# PulseOX.net
KiCad netlist of a schematic drawn in EAGLE
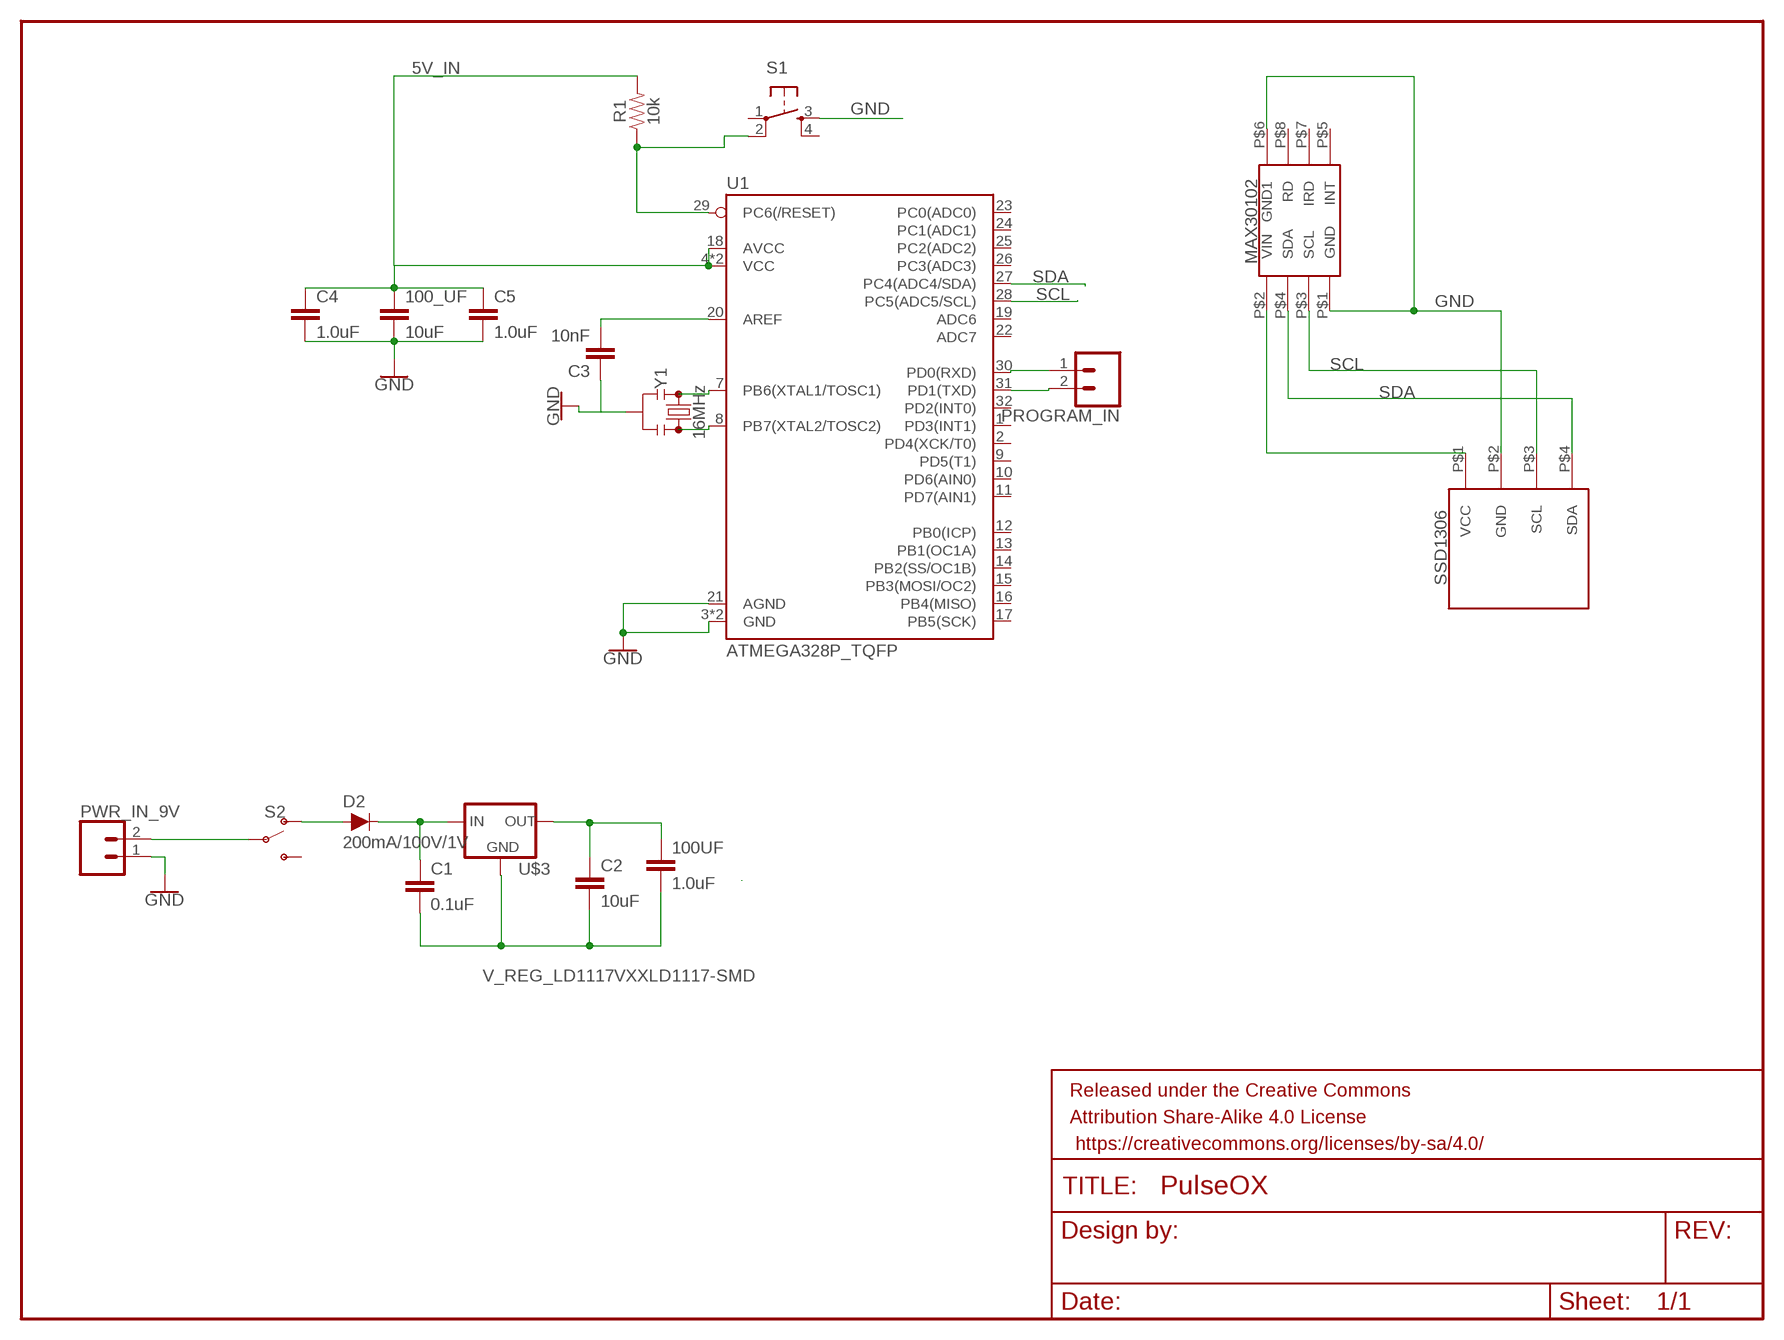
[diagram p0: schematic, sheet 1]

(export (version "E")
  (design (tool "Eeschema 10.0.6"))
  (components
    (comp (ref "100UF")
      (value "1.0uF")
      (footprint "eagle-import:1206")
      (libsource (lib "eagle-import") (part "1.0UF-1206-50V-10%"))
    )
    (comp (ref "100_UF")
      (value "10uF")
      (footprint "eagle-import:1206")
      (libsource (lib "eagle-import") (part "10UF-1206-6.3V-20%"))
    )
    (comp (ref "C1")
      (value "0.1uF")
      (footprint "eagle-import:0603")
      (libsource (lib "eagle-import") (part "0.1UF-0603-25V-(+80/-20%)"))
    )
    (comp (ref "C2")
      (value "10uF")
      (footprint "eagle-import:0603")
      (libsource (lib "eagle-import") (part "10UF-0603-6.3V-20%"))
    )
    (comp (ref "C3")
      (value "10nF")
      (footprint "eagle-import:0603")
      (libsource (lib "eagle-import") (part "10NF-0603-50V-10%"))
    )
    (comp (ref "C4")
      (value "1.0uF")
      (footprint "eagle-import:0603")
      (libsource (lib "eagle-import") (part "1.0UF-0603-16V-10%"))
    )
    (comp (ref "C5")
      (value "1.0uF")
      (footprint "eagle-import:0603")
      (libsource (lib "eagle-import") (part "1.0UF-0603-16V-10%"))
    )
    (comp (ref "D2")
      (value "200mA/100V/1V")
      (footprint "eagle-import:DIODE-1N4148")
      (libsource (lib "eagle-import") (part "DIODE-1N4148"))
    )
    (comp (ref "FRAME1")
      (value "FRAME-LETTER")
      (footprint "eagle-import:CREATIVE_COMMONS")
      (libsource (lib "eagle-import") (part "FRAME-LETTER"))
    )
    (comp (ref "PROGRAM_IN")
      (value "CONN_02")
      (footprint "eagle-import:1X02")
      (libsource (lib "eagle-import") (part "CONN_02"))
    )
    (comp (ref "PWR_IN_9V")
      (value "CONN_02")
      (footprint "eagle-import:1X02")
      (libsource (lib "eagle-import") (part "CONN_02"))
    )
    (comp (ref "R1")
      (value "10k")
      (footprint "eagle-import:0603")
      (libsource (lib "eagle-import") (part "10KOHM-0603-1/10W-1%"))
    )
    (comp (ref "S1")
      (value "TAC_SWITCHPTH")
      (footprint "eagle-import:TACTILE-PTH")
      (libsource (lib "eagle-import") (part "TAC_SWITCHPTH"))
    )
    (comp (ref "S2")
      (value "SWITCH-SPDT-PTH-11.6X4.0MM")
      (footprint "eagle-import:SWITCH_SPDT_PTH_11.6X4.0MM")
      (libsource (lib "eagle-import") (part "SWITCH-SPDT-PTH-11.6X4.0MM"))
    )
    (comp (ref "U$1")
      (value "MAX30102")
      (footprint "eagle-import:MAX30102")
      (libsource (lib "eagle-import") (part "MAX30102"))
    )
    (comp (ref "U$2")
      (value "SSD1306")
      (footprint "eagle-import:SSD1306")
      (libsource (lib "eagle-import") (part "SSD1306"))
    )
    (comp (ref "U$3")
      (value "V_REG_LD1117VXXLD1117-SMD")
      (footprint "eagle-import:SOT223")
      (libsource (lib "eagle-import") (part "V_REG_LD1117VXXLD1117-SMD"))
    )
    (comp (ref "U1")
      (value "ATMEGA328P_TQFP")
      (footprint "eagle-import:TQFP32-08")
      (libsource (lib "eagle-import") (part "ATMEGA328P_TQFP"))
    )
    (comp (ref "Y1")
      (value "16MHz")
      (footprint "eagle-import:RESONATOR-SMD-3.2X1.3")
      (libsource (lib "eagle-import") (part "RESONATOR-16MHZSMD_3.2X1.3"))
    )
  )
  (nets
    (net (code "1") (name "/5V_IN") (class "Default")
      (node (ref "100_UF") (pin "1") (pinfunction "1_1") (pintype "passive"))
      (node (ref "C4") (pin "1") (pinfunction "1_1") (pintype "passive"))
      (node (ref "C5") (pin "1") (pinfunction "1_1") (pintype "passive"))
      (node (ref "R1") (pin "2") (pinfunction "2_2") (pintype "passive"))
      (node (ref "U1") (pin "18") (pinfunction "AVCC_18") (pintype "bidirectional"))
      (node (ref "U1") (pin "4") (pinfunction "VCC_4") (pintype "bidirectional"))
      (node (ref "U1") (pin "6") (pinfunction "VCC_6") (pintype "bidirectional"))
    )
    (net (code "2") (name "/SCL") (class "Default")
      (node (ref "U$1") (pin "P$3") (pinfunction "SCL_P$3") (pintype "bidirectional"))
      (node (ref "U$2") (pin "P$3") (pinfunction "SCL_P$3") (pintype "bidirectional"))
      (node (ref "U1") (pin "28") (pinfunction "PC5(ADC5/SCL)_28") (pintype "bidirectional"))
    )
    (net (code "3") (name "/SDA") (class "Default")
      (node (ref "U$1") (pin "P$4") (pinfunction "SDA_P$4") (pintype "bidirectional"))
      (node (ref "U$2") (pin "P$4") (pinfunction "SDA_P$4") (pintype "bidirectional"))
      (node (ref "U1") (pin "27") (pinfunction "PC4(ADC4/SDA)_27") (pintype "bidirectional"))
    )
    (net (code "4") (name "GND") (class "Default")
      (node (ref "100_UF") (pin "2") (pinfunction "2_2") (pintype "passive"))
      (node (ref "C3") (pin "1") (pinfunction "1_1") (pintype "passive"))
      (node (ref "C4") (pin "2") (pinfunction "2_2") (pintype "passive"))
      (node (ref "C5") (pin "2") (pinfunction "2_2") (pintype "passive"))
      (node (ref "PWR_IN_9V") (pin "1") (pinfunction "1_1") (pintype "passive"))
      (node (ref "S1") (pin "3") (pinfunction "3_3") (pintype "passive"))
      (node (ref "U$1") (pin "P$1") (pinfunction "GND_P$1") (pintype "bidirectional"))
      (node (ref "U$1") (pin "P$6") (pinfunction "GND1_P$6") (pintype "bidirectional"))
      (node (ref "U$2") (pin "P$2") (pinfunction "GND_P$2") (pintype "bidirectional"))
      (node (ref "U1") (pin "21") (pinfunction "AGND_21") (pintype "bidirectional"))
      (node (ref "U1") (pin "3") (pinfunction "GND_3") (pintype "bidirectional"))
      (node (ref "U1") (pin "5") (pinfunction "GND_5") (pintype "bidirectional"))
      (node (ref "Y1") (pin "2") (pinfunction "2_2") (pintype "passive"))
    )
    (net (code "5") (name "Net-(S2-O)") (class "Default")
      (node (ref "D2") (pin "A") (pinfunction "A_A") (pintype "passive"))
      (node (ref "S2") (pin "1") (pinfunction "O_1") (pintype "passive"))
    )
    (net (code "6") (name "Net-(S2-P)") (class "Default")
      (node (ref "PWR_IN_9V") (pin "2") (pinfunction "2_2") (pintype "passive"))
      (node (ref "S2") (pin "2") (pinfunction "P_2") (pintype "passive"))
    )
    (net (code "7") (name "Net-(U$1-VIN)") (class "Default")
      (node (ref "U$1") (pin "P$2") (pinfunction "VIN_P$2") (pintype "bidirectional"))
      (node (ref "U$2") (pin "P$1") (pinfunction "VCC_P$1") (pintype "bidirectional"))
    )
    (net (code "8") (name "Net-(U$3-GND)") (class "Default")
      (node (ref "100UF") (pin "2") (pinfunction "2_2") (pintype "passive"))
      (node (ref "C1") (pin "2") (pinfunction "2_2") (pintype "passive"))
      (node (ref "C2") (pin "2") (pinfunction "2_2") (pintype "passive"))
      (node (ref "U$3") (pin "1") (pinfunction "GND_1") (pintype "input"))
    )
    (net (code "9") (name "Net-(U$3-IN)") (class "Default")
      (node (ref "C1") (pin "1") (pinfunction "1_1") (pintype "passive"))
      (node (ref "D2") (pin "C") (pinfunction "C_C") (pintype "passive"))
      (node (ref "U$3") (pin "3") (pinfunction "IN_3") (pintype "input"))
    )
    (net (code "10") (name "Net-(U$3-OUT)") (class "Default")
      (node (ref "100UF") (pin "1") (pinfunction "1_1") (pintype "passive"))
      (node (ref "C2") (pin "1") (pinfunction "1_1") (pintype "passive"))
      (node (ref "U$3") (pin "2") (pinfunction "OUT_2") (pintype "passive"))
    )
    (net (code "11") (name "Net-(U1-AREF)") (class "Default")
      (node (ref "C3") (pin "2") (pinfunction "2_2") (pintype "passive"))
      (node (ref "U1") (pin "20") (pinfunction "AREF_20") (pintype "bidirectional"))
    )
    (net (code "12") (name "Net-(U1-PB6(XTAL1{slash}TOSC1))") (class "Default")
      (node (ref "U1") (pin "7") (pinfunction "PB6(XTAL1/TOSC1)_7") (pintype "bidirectional"))
      (node (ref "Y1") (pin "1") (pinfunction "1_1") (pintype "passive"))
    )
    (net (code "13") (name "Net-(U1-PB7(XTAL2{slash}TOSC2))") (class "Default")
      (node (ref "U1") (pin "8") (pinfunction "PB7(XTAL2/TOSC2)_8") (pintype "bidirectional"))
      (node (ref "Y1") (pin "3") (pinfunction "3_3") (pintype "passive"))
    )
    (net (code "14") (name "Net-(U1-PC6({slash}RESET))") (class "Default")
      (node (ref "R1") (pin "1") (pinfunction "1_1") (pintype "passive"))
      (node (ref "S1") (pin "2") (pinfunction "2_2") (pintype "passive"))
      (node (ref "U1") (pin "29") (pinfunction "PC6(/RESET)_29") (pintype "bidirectional"))
    )
    (net (code "15") (name "Net-(U1-PD0(RXD))") (class "Default")
      (node (ref "PROGRAM_IN") (pin "1") (pinfunction "1_1") (pintype "passive"))
      (node (ref "U1") (pin "30") (pinfunction "PD0(RXD)_30") (pintype "bidirectional"))
    )
    (net (code "16") (name "Net-(U1-PD1(TXD))") (class "Default")
      (node (ref "PROGRAM_IN") (pin "2") (pinfunction "2_2") (pintype "passive"))
      (node (ref "U1") (pin "31") (pinfunction "PD1(TXD)_31") (pintype "bidirectional"))
    )
    (net (code "17") (name "unconnected-(S1-Pad1)") (class "Default")
      (node (ref "S1") (pin "1") (pinfunction "1_1") (pintype "passive"))
    )
    (net (code "18") (name "unconnected-(S1-Pad4)") (class "Default")
      (node (ref "S1") (pin "4") (pinfunction "4_4") (pintype "passive"))
    )
    (net (code "19") (name "unconnected-(S2-S-Pad3)") (class "Default")
      (node (ref "S2") (pin "3") (pinfunction "S_3") (pintype "passive"))
    )
    (net (code "20") (name "unconnected-(U$1-INT-PadP$5)") (class "Default")
      (node (ref "U$1") (pin "P$5") (pinfunction "INT_P$5") (pintype "bidirectional"))
    )
    (net (code "21") (name "unconnected-(U$1-IRD-PadP$7)") (class "Default")
      (node (ref "U$1") (pin "P$7") (pinfunction "IRD_P$7") (pintype "bidirectional"))
    )
    (net (code "22") (name "unconnected-(U$1-RD-PadP$8)") (class "Default")
      (node (ref "U$1") (pin "P$8") (pinfunction "RD_P$8") (pintype "bidirectional"))
    )
    (net (code "23") (name "unconnected-(U1-ADC6-Pad19)") (class "Default")
      (node (ref "U1") (pin "19") (pinfunction "ADC6_19") (pintype "bidirectional"))
    )
    (net (code "24") (name "unconnected-(U1-ADC7-Pad22)") (class "Default")
      (node (ref "U1") (pin "22") (pinfunction "ADC7_22") (pintype "bidirectional"))
    )
    (net (code "25") (name "unconnected-(U1-PB0(ICP)-Pad12)") (class "Default")
      (node (ref "U1") (pin "12") (pinfunction "PB0(ICP)_12") (pintype "bidirectional"))
    )
    (net (code "26") (name "unconnected-(U1-PB1(OC1A)-Pad13)") (class "Default")
      (node (ref "U1") (pin "13") (pinfunction "PB1(OC1A)_13") (pintype "bidirectional"))
    )
    (net (code "27") (name "unconnected-(U1-PB2(SS{slash}OC1B)-Pad14)") (class "Default")
      (node (ref "U1") (pin "14") (pinfunction "PB2(SS/OC1B)_14") (pintype "bidirectional"))
    )
    (net (code "28") (name "unconnected-(U1-PB3(MOSI{slash}OC2)-Pad15)") (class "Default")
      (node (ref "U1") (pin "15") (pinfunction "PB3(MOSI/OC2)_15") (pintype "bidirectional"))
    )
    (net (code "29") (name "unconnected-(U1-PB4(MISO)-Pad16)") (class "Default")
      (node (ref "U1") (pin "16") (pinfunction "PB4(MISO)_16") (pintype "bidirectional"))
    )
    (net (code "30") (name "unconnected-(U1-PB5(SCK)-Pad17)") (class "Default")
      (node (ref "U1") (pin "17") (pinfunction "PB5(SCK)_17") (pintype "bidirectional"))
    )
    (net (code "31") (name "unconnected-(U1-PC0(ADC0)-Pad23)") (class "Default")
      (node (ref "U1") (pin "23") (pinfunction "PC0(ADC0)_23") (pintype "bidirectional"))
    )
    (net (code "32") (name "unconnected-(U1-PC1(ADC1)-Pad24)") (class "Default")
      (node (ref "U1") (pin "24") (pinfunction "PC1(ADC1)_24") (pintype "bidirectional"))
    )
    (net (code "33") (name "unconnected-(U1-PC2(ADC2)-Pad25)") (class "Default")
      (node (ref "U1") (pin "25") (pinfunction "PC2(ADC2)_25") (pintype "bidirectional"))
    )
    (net (code "34") (name "unconnected-(U1-PC3(ADC3)-Pad26)") (class "Default")
      (node (ref "U1") (pin "26") (pinfunction "PC3(ADC3)_26") (pintype "bidirectional"))
    )
    (net (code "35") (name "unconnected-(U1-PD2(INT0)-Pad32)") (class "Default")
      (node (ref "U1") (pin "32") (pinfunction "PD2(INT0)_32") (pintype "bidirectional"))
    )
    (net (code "36") (name "unconnected-(U1-PD3(INT1)-Pad1)") (class "Default")
      (node (ref "U1") (pin "1") (pinfunction "PD3(INT1)_1") (pintype "bidirectional"))
    )
    (net (code "37") (name "unconnected-(U1-PD4(XCK{slash}T0)-Pad2)") (class "Default")
      (node (ref "U1") (pin "2") (pinfunction "PD4(XCK/T0)_2") (pintype "bidirectional"))
    )
    (net (code "38") (name "unconnected-(U1-PD5(T1)-Pad9)") (class "Default")
      (node (ref "U1") (pin "9") (pinfunction "PD5(T1)_9") (pintype "bidirectional"))
    )
    (net (code "39") (name "unconnected-(U1-PD6(AIN0)-Pad10)") (class "Default")
      (node (ref "U1") (pin "10") (pinfunction "PD6(AIN0)_10") (pintype "bidirectional"))
    )
    (net (code "40") (name "unconnected-(U1-PD7(AIN1)-Pad11)") (class "Default")
      (node (ref "U1") (pin "11") (pinfunction "PD7(AIN1)_11") (pintype "bidirectional"))
    )
  )
)
